# Microcontroller.net
KiCad netlist of a schematic drawn in Altium Designer
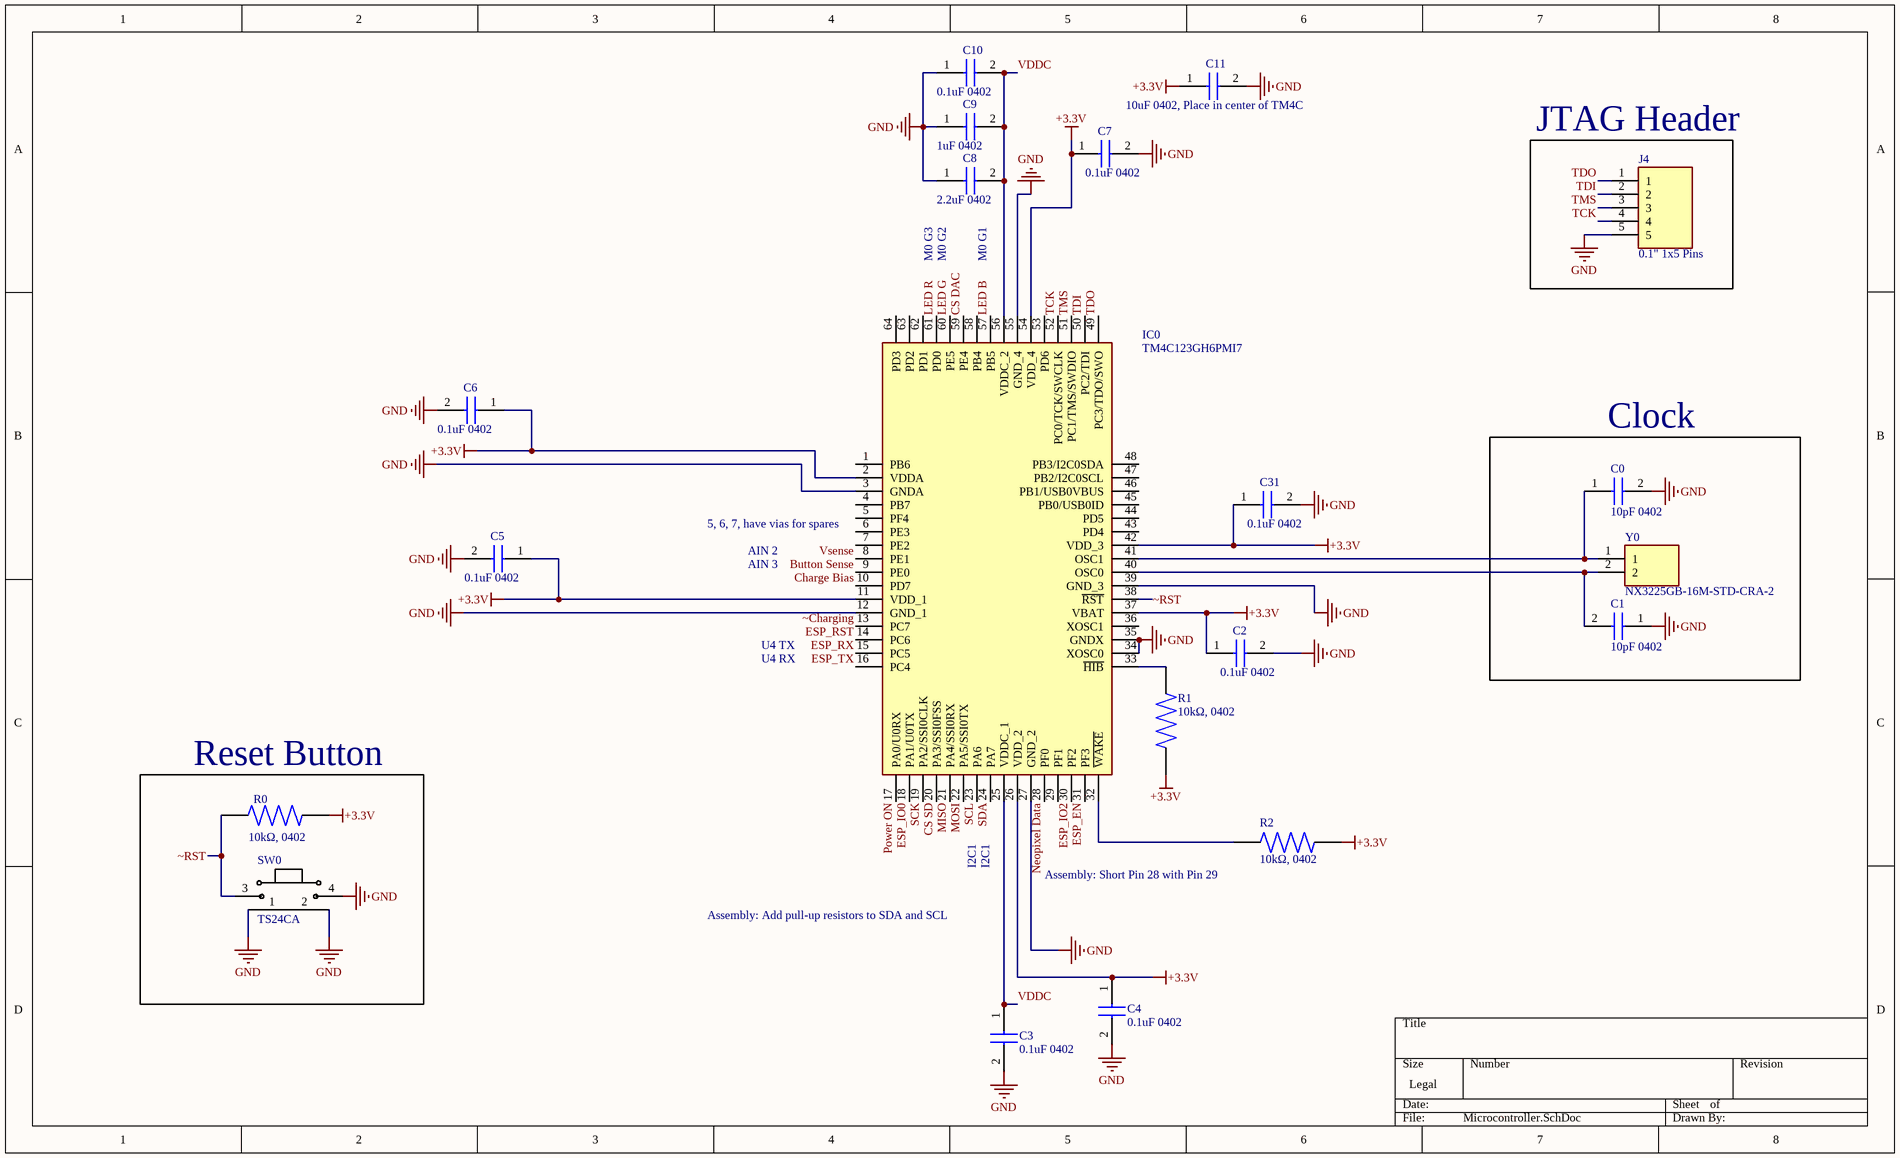
[diagram p0: Microcontroller.SchDoc]

(export (version "E")
  (design (tool "Eeschema 10.0.6"))
  (components
    (comp (ref "C0")
      (value "10pF 0402")
      (footprint "SamacSys:CAPC1005X56N")
      (description "Capacitor")
      (fields
        (field (name "MANUFACTURER_PART_NUMBER") "04025A100BAT2A")
        (field (name "MOUSER PART NUMBER") "581-04025A100B")
      )
      (libsource (lib "*") (part "04025A100BAT2A"))
    )
    (comp (ref "C1")
      (value "10pF 0402")
      (footprint "SamacSys:CAPC1005X56N")
      (description "Capacitor")
      (fields
        (field (name "MANUFACTURER_PART_NUMBER") "04025A100BAT2A")
        (field (name "MOUSER PART NUMBER") "581-04025A100B")
      )
      (libsource (lib "*") (part "04025A100BAT2A"))
    )
    (comp (ref "C2")
      (value "0.1uF 0402")
      (footprint "SamacSys:CAPC1005X56N")
      (description "Capacitor")
      (fields
        (field (name "MANUFACTURER_PART_NUMBER") "04025A100BAT2A")
        (field (name "MOUSER PART NUMBER") "581-04025A100B")
      )
      (libsource (lib "*") (part "04025A100BAT2A"))
    )
    (comp (ref "C3")
      (value "0.1uF 0402")
      (footprint "SamacSys:CAPC1005X56N")
      (description "Capacitor")
      (fields
        (field (name "MANUFACTURER_PART_NUMBER") "04025A100BAT2A")
        (field (name "MOUSER PART NUMBER") "581-04025A100B")
      )
      (libsource (lib "*") (part "04025A100BAT2A"))
    )
    (comp (ref "C4")
      (value "0.1uF 0402")
      (footprint "SamacSys:CAPC1005X56N")
      (description "Capacitor")
      (fields
        (field (name "MANUFACTURER_PART_NUMBER") "04025A100BAT2A")
        (field (name "MOUSER PART NUMBER") "581-04025A100B")
      )
      (libsource (lib "*") (part "04025A100BAT2A"))
    )
    (comp (ref "C5")
      (value "0.1uF 0402")
      (footprint "SamacSys:CAPC1005X56N")
      (description "Capacitor")
      (fields
        (field (name "MANUFACTURER_PART_NUMBER") "04025A100BAT2A")
        (field (name "MOUSER PART NUMBER") "581-04025A100B")
      )
      (libsource (lib "*") (part "04025A100BAT2A"))
    )
    (comp (ref "C6")
      (value "0.1uF 0402")
      (footprint "SamacSys:CAPC1005X56N")
      (description "Capacitor")
      (fields
        (field (name "MANUFACTURER_PART_NUMBER") "04025A100BAT2A")
        (field (name "MOUSER PART NUMBER") "581-04025A100B")
      )
      (libsource (lib "*") (part "04025A100BAT2A"))
    )
    (comp (ref "C7")
      (value "0.1uF 0402")
      (footprint "SamacSys:CAPC1005X56N")
      (description "Capacitor")
      (fields
        (field (name "MANUFACTURER_PART_NUMBER") "04025A100BAT2A")
        (field (name "MOUSER PART NUMBER") "581-04025A100B")
      )
      (libsource (lib "*") (part "04025A100BAT2A"))
    )
    (comp (ref "C8")
      (value "2.2uF 0402")
      (footprint "SamacSys:CAPC1005X56N")
      (description "Capacitor")
      (fields
        (field (name "MANUFACTURER_PART_NUMBER") "04025A100BAT2A")
        (field (name "MOUSER PART NUMBER") "581-04025A100B")
      )
      (libsource (lib "*") (part "04025A100BAT2A"))
    )
    (comp (ref "C9")
      (value "1uF 0402")
      (footprint "SamacSys:CAPC1005X56N")
      (description "Capacitor")
      (fields
        (field (name "MANUFACTURER_PART_NUMBER") "04025A100BAT2A")
        (field (name "MOUSER PART NUMBER") "581-04025A100B")
      )
      (libsource (lib "*") (part "04025A100BAT2A"))
    )
    (comp (ref "C10")
      (value "0.1uF 0402")
      (footprint "SamacSys:CAPC1005X56N")
      (description "Capacitor")
      (fields
        (field (name "MANUFACTURER_PART_NUMBER") "04025A100BAT2A")
        (field (name "MOUSER PART NUMBER") "581-04025A100B")
      )
      (libsource (lib "*") (part "04025A100BAT2A"))
    )
    (comp (ref "C11")
      (value "10uF 0402, Place in center of TM4C")
      (footprint "SamacSys:CAPC1005X56N")
      (description "Capacitor")
      (fields
        (field (name "MANUFACTURER_PART_NUMBER") "04025A100BAT2A")
        (field (name "MOUSER PART NUMBER") "581-04025A100B")
      )
      (libsource (lib "*") (part "04025A100BAT2A"))
    )
    (comp (ref "C31")
      (value "0.1uF 0402")
      (footprint "SamacSys:CAPC1005X56N")
      (description "Capacitor")
      (fields
        (field (name "MANUFACTURER_PART_NUMBER") "04025A100BAT2A")
        (field (name "MOUSER PART NUMBER") "581-04025A100B")
      )
      (libsource (lib "*") (part "04025A100BAT2A"))
    )
    (comp (ref "IC0")
      (value "TM4C123GH6PMI7")
      (footprint "SamacSys:QFP50P1200X1200X160-64N")
      (description "Integrated Circuit")
      (fields (field (name "MOUSER PART NUMBER") "595-TM4C123GH6PMI7"))
      (libsource (lib "*") (part "TM4C123GH6PMI7"))
    )
    (comp (ref "J4")
      (value "0.1\" 1x5 Pins")
      (footprint "SamacSys:HDRV5W64P0X254_1X5_1270X254X610P")
      (description "Connector")
      (fields
        (field (name "MANUFACTURER_PART_NUMBER") "M20-9990546")
        (field (name "MOUSER PART NUMBER") "855-M20-9990546")
      )
      (libsource (lib "*") (part "M20-9990546"))
    )
    (comp (ref "R0")
      (value "10kΩ, 0402")
      (footprint "0402")
      (libsource (lib "Lightsaber") (part "Resistor, 0402"))
    )
    (comp (ref "R1")
      (value "10kΩ, 0402")
      (footprint "0402")
      (libsource (lib "Lightsaber") (part "Resistor, 0402"))
    )
    (comp (ref "R2")
      (value "10kΩ, 0402")
      (footprint "0402")
      (libsource (lib "Lightsaber") (part "Resistor, 0402"))
    )
    (comp (ref "SW0") (value "TS24CA") (footprint "TS24CA") (libsource (lib "Lightsaber") (part "TS24CA")))
    (comp (ref "Y0")
      (value "NX3225GB-16M-STD-CRA-2")
      (footprint "SamacSys:NX3225GD-STD-CRA-3")
      (description "Crystal or Oscillator")
      (fields (field (name "MOUSER PART NUMBER") "344-NX3225GB16MSTRA2"))
      (libsource (lib "*") (part "NX3225GB-16M-STD-CRA-2"))
    )
  )
  (nets
    (net (code "1") (name "+3.3V") (class "Default")
      (node (ref "C11") (pin "1") (pinfunction "1_1") (pintype "passive"))
      (node (ref "C2") (pin "1") (pinfunction "1_1") (pintype "passive"))
      (node (ref "C31") (pin "1") (pinfunction "1_1") (pintype "passive"))
      (node (ref "C4") (pin "1") (pinfunction "1_1") (pintype "passive"))
      (node (ref "C5") (pin "1") (pinfunction "1_1") (pintype "passive"))
      (node (ref "C6") (pin "1") (pinfunction "1_1") (pintype "passive"))
      (node (ref "C7") (pin "1") (pinfunction "1_1") (pintype "passive"))
      (node (ref "IC0") (pin "11") (pinfunction "VDD_1_11") (pintype "passive"))
      (node (ref "IC0") (pin "2") (pinfunction "VDDA_2") (pintype "passive"))
      (node (ref "IC0") (pin "26") (pinfunction "VDD_2_26") (pintype "passive"))
      (node (ref "IC0") (pin "37") (pinfunction "VBAT_37") (pintype "passive"))
      (node (ref "IC0") (pin "42") (pinfunction "VDD_3_42") (pintype "passive"))
      (node (ref "IC0") (pin "54") (pinfunction "VDD_4_54") (pintype "passive"))
      (node (ref "R0") (pin "2") (pinfunction "2_2") (pintype "passive"))
      (node (ref "R1") (pin "2") (pinfunction "2_2") (pintype "passive"))
      (node (ref "R2") (pin "2") (pinfunction "2_2") (pintype "passive"))
    )
    (net (code "2") (name "/Button Sense") (class "Default")
      (node (ref "IC0") (pin "9") (pinfunction "PE0_9") (pintype "passive"))
    )
    (net (code "3") (name "/CS DAC") (class "Default")
      (node (ref "IC0") (pin "59") (pinfunction "PE4_59") (pintype "passive"))
    )
    (net (code "4") (name "/CS SD") (class "Default")
      (node (ref "IC0") (pin "20") (pinfunction "PA3/SSI0FSS_20") (pintype "passive"))
    )
    (net (code "5") (name "/Charge Bias") (class "Default")
      (node (ref "IC0") (pin "10") (pinfunction "PD7_10") (pintype "passive"))
    )
    (net (code "6") (name "/ESP_EN") (class "Default")
      (node (ref "IC0") (pin "31") (pinfunction "PF3_31") (pintype "passive"))
    )
    (net (code "7") (name "/ESP_IO0") (class "Default")
      (node (ref "IC0") (pin "18") (pinfunction "PA1/U0TX_18") (pintype "passive"))
    )
    (net (code "8") (name "/ESP_IO2") (class "Default")
      (node (ref "IC0") (pin "30") (pinfunction "PF2_30") (pintype "passive"))
    )
    (net (code "9") (name "/ESP_RST") (class "Default")
      (node (ref "IC0") (pin "14") (pinfunction "PC6_14") (pintype "passive"))
    )
    (net (code "10") (name "/ESP_RX") (class "Default")
      (node (ref "IC0") (pin "15") (pinfunction "PC5_15") (pintype "passive"))
    )
    (net (code "11") (name "/ESP_TX") (class "Default")
      (node (ref "IC0") (pin "16") (pinfunction "PC4_16") (pintype "passive"))
    )
    (net (code "12") (name "/LED B") (class "Default")
      (node (ref "IC0") (pin "57") (pinfunction "PB5_57") (pintype "passive"))
    )
    (net (code "13") (name "/LED G") (class "Default")
      (node (ref "IC0") (pin "60") (pinfunction "PE5_60") (pintype "passive"))
    )
    (net (code "14") (name "/LED R") (class "Default")
      (node (ref "IC0") (pin "61") (pinfunction "PD0_61") (pintype "passive"))
    )
    (net (code "15") (name "/MISO") (class "Default")
      (node (ref "IC0") (pin "21") (pinfunction "PA4/SSI0RX_21") (pintype "passive"))
    )
    (net (code "16") (name "/MOSI") (class "Default")
      (node (ref "IC0") (pin "22") (pinfunction "PA5/SSI0TX_22") (pintype "passive"))
    )
    (net (code "17") (name "/Neopixel Data") (class "Default")
      (node (ref "IC0") (pin "28") (pinfunction "PF0_28") (pintype "passive"))
    )
    (net (code "18") (name "/Power ON") (class "Default")
      (node (ref "IC0") (pin "17") (pinfunction "PA0/U0RX_17") (pintype "passive"))
    )
    (net (code "19") (name "/SCK") (class "Default")
      (node (ref "IC0") (pin "19") (pinfunction "PA2/SSI0CLK_19") (pintype "passive"))
    )
    (net (code "20") (name "/SCL") (class "Default")
      (node (ref "IC0") (pin "23") (pinfunction "PA6_23") (pintype "passive"))
    )
    (net (code "21") (name "/SDA") (class "Default")
      (node (ref "IC0") (pin "24") (pinfunction "PA7_24") (pintype "passive"))
    )
    (net (code "22") (name "/TCK") (class "Default")
      (node (ref "IC0") (pin "52") (pinfunction "PC0/TCK/SWCLK_52") (pintype "passive"))
      (node (ref "J4") (pin "4") (pinfunction "4_4") (pintype "passive"))
    )
    (net (code "23") (name "/TDI") (class "Default")
      (node (ref "IC0") (pin "50") (pinfunction "PC2/TDI_50") (pintype "passive"))
      (node (ref "J4") (pin "2") (pinfunction "2_2") (pintype "passive"))
    )
    (net (code "24") (name "/TDO") (class "Default")
      (node (ref "IC0") (pin "49") (pinfunction "PC3/TDO/SWO_49") (pintype "passive"))
      (node (ref "J4") (pin "1") (pinfunction "1_1") (pintype "passive"))
    )
    (net (code "25") (name "/TMS") (class "Default")
      (node (ref "IC0") (pin "51") (pinfunction "PC1/TMS/SWDIO_51") (pintype "passive"))
      (node (ref "J4") (pin "3") (pinfunction "3_3") (pintype "passive"))
    )
    (net (code "26") (name "/VDDC") (class "Default")
      (node (ref "C10") (pin "2") (pinfunction "2_2") (pintype "passive"))
      (node (ref "C3") (pin "1") (pinfunction "1_1") (pintype "passive"))
      (node (ref "C8") (pin "2") (pinfunction "2_2") (pintype "passive"))
      (node (ref "C9") (pin "2") (pinfunction "2_2") (pintype "passive"))
      (node (ref "IC0") (pin "25") (pinfunction "VDDC_1_25") (pintype "passive"))
      (node (ref "IC0") (pin "56") (pinfunction "VDDC_2_56") (pintype "passive"))
    )
    (net (code "27") (name "/Vsense") (class "Default")
      (node (ref "IC0") (pin "8") (pinfunction "PE1_8") (pintype "passive"))
    )
    (net (code "28") (name "/~Charging") (class "Default")
      (node (ref "IC0") (pin "13") (pinfunction "PC7_13") (pintype "passive"))
    )
    (net (code "29") (name "/~RST") (class "Default")
      (node (ref "IC0") (pin "38") (pinfunction "~{RST}_38") (pintype "passive"))
      (node (ref "R0") (pin "1") (pinfunction "1_1") (pintype "passive"))
      (node (ref "SW0") (pin "3") (pintype "passive"))
    )
    (net (code "30") (name "GND") (class "Default")
      (node (ref "C0") (pin "2") (pinfunction "2_2") (pintype "passive"))
      (node (ref "C1") (pin "1") (pinfunction "1_1") (pintype "passive"))
      (node (ref "C10") (pin "1") (pinfunction "1_1") (pintype "passive"))
      (node (ref "C11") (pin "2") (pinfunction "2_2") (pintype "passive"))
      (node (ref "C2") (pin "2") (pinfunction "2_2") (pintype "passive"))
      (node (ref "C3") (pin "2") (pinfunction "2_2") (pintype "passive"))
      (node (ref "C31") (pin "2") (pinfunction "2_2") (pintype "passive"))
      (node (ref "C4") (pin "2") (pinfunction "2_2") (pintype "passive"))
      (node (ref "C5") (pin "2") (pinfunction "2_2") (pintype "passive"))
      (node (ref "C6") (pin "2") (pinfunction "2_2") (pintype "passive"))
      (node (ref "C7") (pin "2") (pinfunction "2_2") (pintype "passive"))
      (node (ref "C8") (pin "1") (pinfunction "1_1") (pintype "passive"))
      (node (ref "C9") (pin "1") (pinfunction "1_1") (pintype "passive"))
      (node (ref "IC0") (pin "12") (pinfunction "GND_1_12") (pintype "passive"))
      (node (ref "IC0") (pin "27") (pinfunction "GND_2_27") (pintype "passive"))
      (node (ref "IC0") (pin "3") (pinfunction "GNDA_3") (pintype "passive"))
      (node (ref "IC0") (pin "34") (pinfunction "XOSC0_34") (pintype "passive"))
      (node (ref "IC0") (pin "35") (pinfunction "GNDX_35") (pintype "passive"))
      (node (ref "IC0") (pin "39") (pinfunction "GND_3_39") (pintype "passive"))
      (node (ref "IC0") (pin "55") (pinfunction "GND_4_55") (pintype "passive"))
      (node (ref "J4") (pin "5") (pinfunction "5_5") (pintype "passive"))
      (node (ref "SW0") (pin "1") (pinfunction "1_1") (pintype "passive"))
      (node (ref "SW0") (pin "2") (pinfunction "2_2") (pintype "passive"))
      (node (ref "SW0") (pin "4") (pinfunction "4_4") (pintype "passive"))
    )
    (net (code "31") (name "Net-(IC0-OSC0)") (class "Default")
      (node (ref "C1") (pin "2") (pinfunction "2_2") (pintype "passive"))
      (node (ref "IC0") (pin "40") (pinfunction "OSC0_40") (pintype "passive"))
      (node (ref "Y0") (pin "2") (pinfunction "2_2") (pintype "passive"))
    )
    (net (code "32") (name "Net-(IC0-OSC1)") (class "Default")
      (node (ref "C0") (pin "1") (pinfunction "1_1") (pintype "passive"))
      (node (ref "IC0") (pin "41") (pinfunction "OSC1_41") (pintype "passive"))
      (node (ref "Y0") (pin "1") (pinfunction "1_1") (pintype "passive"))
    )
    (net (code "33") (name "Net-(IC0-~{HIB})") (class "Default")
      (node (ref "IC0") (pin "33") (pinfunction "~{HIB}_33") (pintype "passive"))
      (node (ref "R1") (pin "1") (pinfunction "1_1") (pintype "passive"))
    )
    (net (code "34") (name "Net-(IC0-~{WAKE})") (class "Default")
      (node (ref "IC0") (pin "32") (pinfunction "~{WAKE}_32") (pintype "passive"))
      (node (ref "R2") (pin "1") (pinfunction "1_1") (pintype "passive"))
    )
    (net (code "35") (name "unconnected-(IC0-PB0{slash}USB0ID-Pad45)") (class "Default")
      (node (ref "IC0") (pin "45") (pinfunction "PB0/USB0ID_45") (pintype "passive"))
    )
    (net (code "36") (name "unconnected-(IC0-PB1{slash}USB0VBUS-Pad46)") (class "Default")
      (node (ref "IC0") (pin "46") (pinfunction "PB1/USB0VBUS_46") (pintype "passive"))
    )
    (net (code "37") (name "unconnected-(IC0-PB2{slash}I2C0SCL-Pad47)") (class "Default")
      (node (ref "IC0") (pin "47") (pinfunction "PB2/I2C0SCL_47") (pintype "passive"))
    )
    (net (code "38") (name "unconnected-(IC0-PB3{slash}I2C0SDA-Pad48)") (class "Default")
      (node (ref "IC0") (pin "48") (pinfunction "PB3/I2C0SDA_48") (pintype "passive"))
    )
    (net (code "39") (name "unconnected-(IC0-PB4-Pad58)") (class "Default")
      (node (ref "IC0") (pin "58") (pinfunction "PB4_58") (pintype "passive"))
    )
    (net (code "40") (name "unconnected-(IC0-PB6-Pad1)") (class "Default")
      (node (ref "IC0") (pin "1") (pinfunction "PB6_1") (pintype "passive"))
    )
    (net (code "41") (name "unconnected-(IC0-PB7-Pad4)") (class "Default")
      (node (ref "IC0") (pin "4") (pinfunction "PB7_4") (pintype "passive"))
    )
    (net (code "42") (name "unconnected-(IC0-PD1-Pad62)") (class "Default")
      (node (ref "IC0") (pin "62") (pinfunction "PD1_62") (pintype "passive"))
    )
    (net (code "43") (name "unconnected-(IC0-PD2-Pad63)") (class "Default")
      (node (ref "IC0") (pin "63") (pinfunction "PD2_63") (pintype "passive"))
    )
    (net (code "44") (name "unconnected-(IC0-PD3-Pad64)") (class "Default")
      (node (ref "IC0") (pin "64") (pinfunction "PD3_64") (pintype "passive"))
    )
    (net (code "45") (name "unconnected-(IC0-PD4-Pad43)") (class "Default")
      (node (ref "IC0") (pin "43") (pinfunction "PD4_43") (pintype "passive"))
    )
    (net (code "46") (name "unconnected-(IC0-PD5-Pad44)") (class "Default")
      (node (ref "IC0") (pin "44") (pinfunction "PD5_44") (pintype "passive"))
    )
    (net (code "47") (name "unconnected-(IC0-PD6-Pad53)") (class "Default")
      (node (ref "IC0") (pin "53") (pinfunction "PD6_53") (pintype "passive"))
    )
    (net (code "48") (name "unconnected-(IC0-PE2-Pad7)") (class "Default")
      (node (ref "IC0") (pin "7") (pinfunction "PE2_7") (pintype "passive"))
    )
    (net (code "49") (name "unconnected-(IC0-PE3-Pad6)") (class "Default")
      (node (ref "IC0") (pin "6") (pinfunction "PE3_6") (pintype "passive"))
    )
    (net (code "50") (name "unconnected-(IC0-PF1-Pad29)") (class "Default")
      (node (ref "IC0") (pin "29") (pinfunction "PF1_29") (pintype "passive"))
    )
    (net (code "51") (name "unconnected-(IC0-PF4-Pad5)") (class "Default")
      (node (ref "IC0") (pin "5") (pinfunction "PF4_5") (pintype "passive"))
    )
    (net (code "52") (name "unconnected-(IC0-XOSC1-Pad36)") (class "Default")
      (node (ref "IC0") (pin "36") (pinfunction "XOSC1_36") (pintype "passive"))
    )
  )
)
